# compressor_poc.net
KiCad netlist of a schematic drawn in EAGLE
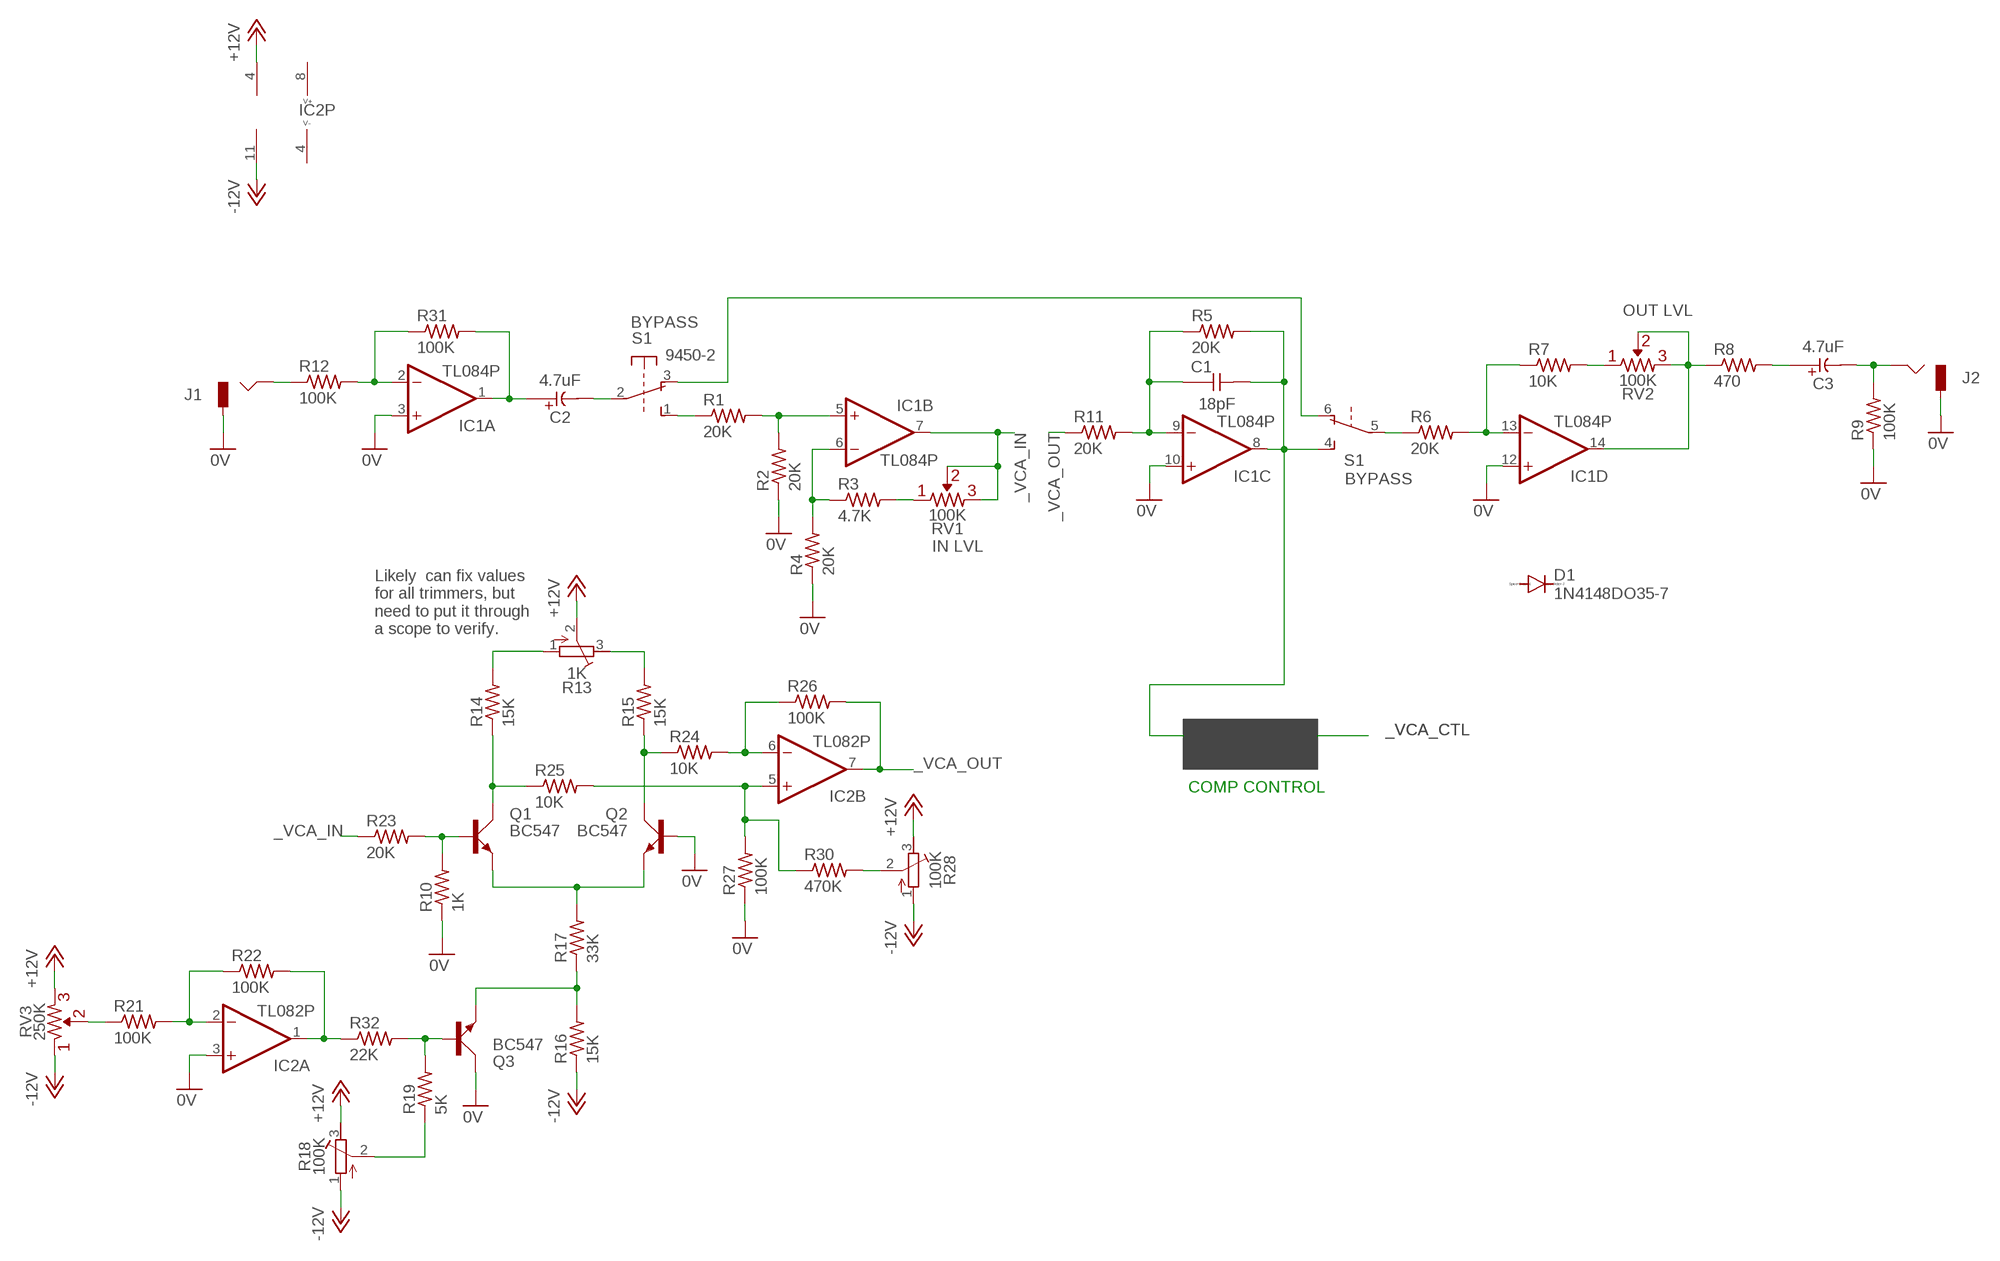
[diagram p0: schematic, sheet 1]

(export (version "E")
  (design (tool "Eeschema 10.0.6"))
  (components
    (comp (ref "C1")
      (value "18pF")
      (footprint "eagle-import:C025-024X044")
      (libsource (lib "eagle-import") (part "CC-US025-024X044"))
    )
    (comp (ref "C2")
      (value "4.7uF")
      (footprint "eagle-import:E2-5")
      (libsource (lib "eagle-import") (part "CE-USE2-5"))
    )
    (comp (ref "C3")
      (value "4.7uF")
      (footprint "eagle-import:E2-5")
      (libsource (lib "eagle-import") (part "CE-USE2-5"))
    )
    (comp (ref "D1")
      (value "1N4148DO35-7")
      (footprint "eagle-import:DO35-7")
      (libsource (lib "eagle-import") (part "1N4148DO35-7"))
    )
    (comp (ref "IC1")
      (value "TL084P")
      (footprint "eagle-import:DIL14")
      (libsource (lib "eagle-import") (part "TL084P"))
    )
    (comp (ref "IC2")
      (value "TL082P")
      (footprint "eagle-import:DIL08")
      (libsource (lib "eagle-import") (part "TL082P"))
    )
    (comp (ref "J1")
      (value "JACK-M")
      (footprint "eagle-import:JACK-M")
      (libsource (lib "eagle-import") (part "JACK-M"))
    )
    (comp (ref "J2")
      (value "JACK-M")
      (footprint "eagle-import:JACK-M")
      (libsource (lib "eagle-import") (part "JACK-M"))
    )
    (comp (ref "Q1")
      (value "BC547")
      (footprint "eagle-import:SOT54A")
      (libsource (lib "eagle-import") (part "BC547"))
    )
    (comp (ref "Q2")
      (value "BC547")
      (footprint "eagle-import:SOT54A")
      (libsource (lib "eagle-import") (part "BC547"))
    )
    (comp (ref "Q3")
      (value "BC547")
      (footprint "eagle-import:SOT54A")
      (libsource (lib "eagle-import") (part "BC547"))
    )
    (comp (ref "R1")
      (value "20K")
      (footprint "eagle-import:0204_7")
      (libsource (lib "eagle-import") (part "R-US_0204/7"))
    )
    (comp (ref "R2")
      (value "20K")
      (footprint "eagle-import:0204_7")
      (libsource (lib "eagle-import") (part "R-US_0204/7"))
    )
    (comp (ref "R3")
      (value "4.7K")
      (footprint "eagle-import:0204_7")
      (libsource (lib "eagle-import") (part "R-US_0204/7"))
    )
    (comp (ref "R4")
      (value "20K")
      (footprint "eagle-import:0204_7")
      (libsource (lib "eagle-import") (part "R-US_0204/7"))
    )
    (comp (ref "R5")
      (value "20K")
      (footprint "eagle-import:0204_7")
      (libsource (lib "eagle-import") (part "R-US_0204/7"))
    )
    (comp (ref "R6")
      (value "20K")
      (footprint "eagle-import:0204_7")
      (libsource (lib "eagle-import") (part "R-US_0204/7"))
    )
    (comp (ref "R7")
      (value "10K")
      (footprint "eagle-import:0204_7")
      (libsource (lib "eagle-import") (part "R-US_0204/7"))
    )
    (comp (ref "R8")
      (value "470")
      (footprint "eagle-import:0204_7")
      (libsource (lib "eagle-import") (part "R-US_0204/7"))
    )
    (comp (ref "R9")
      (value "100K")
      (footprint "eagle-import:0204_7")
      (libsource (lib "eagle-import") (part "R-US_0204/7"))
    )
    (comp (ref "R10")
      (value "1K")
      (footprint "eagle-import:0204_7")
      (libsource (lib "eagle-import") (part "R-US_0204/7"))
    )
    (comp (ref "R11")
      (value "20K")
      (footprint "eagle-import:0204_7")
      (libsource (lib "eagle-import") (part "R-US_0204/7"))
    )
    (comp (ref "R12")
      (value "100K")
      (footprint "eagle-import:0204_7")
      (libsource (lib "eagle-import") (part "R-US_0204/7"))
    )
    (comp (ref "R13")
      (value "1K")
      (footprint "eagle-import:RTRIM3304W")
      (libsource (lib "eagle-import") (part "R-TRIMM3304W"))
    )
    (comp (ref "R14")
      (value "15K")
      (footprint "eagle-import:0204_7")
      (libsource (lib "eagle-import") (part "R-US_0204/7"))
    )
    (comp (ref "R15")
      (value "15K")
      (footprint "eagle-import:0204_7")
      (libsource (lib "eagle-import") (part "R-US_0204/7"))
    )
    (comp (ref "R16")
      (value "15K")
      (footprint "eagle-import:0204_7")
      (libsource (lib "eagle-import") (part "R-US_0204/7"))
    )
    (comp (ref "R17")
      (value "33K")
      (footprint "eagle-import:0204_7")
      (libsource (lib "eagle-import") (part "R-US_0204/7"))
    )
    (comp (ref "R18")
      (value "100K")
      (footprint "eagle-import:RTRIM3304W")
      (libsource (lib "eagle-import") (part "R-TRIMM3304W"))
    )
    (comp (ref "R19")
      (value "5K")
      (footprint "eagle-import:0204_7")
      (libsource (lib "eagle-import") (part "R-US_0204/7"))
    )
    (comp (ref "R21")
      (value "100K")
      (footprint "eagle-import:0204_7")
      (libsource (lib "eagle-import") (part "R-US_0204/7"))
    )
    (comp (ref "R22")
      (value "100K")
      (footprint "eagle-import:0204_7")
      (libsource (lib "eagle-import") (part "R-US_0204/7"))
    )
    (comp (ref "R23")
      (value "20K")
      (footprint "eagle-import:0204_7")
      (libsource (lib "eagle-import") (part "R-US_0204/7"))
    )
    (comp (ref "R24")
      (value "10K")
      (footprint "eagle-import:0204_7")
      (libsource (lib "eagle-import") (part "R-US_0204/7"))
    )
    (comp (ref "R25")
      (value "10K")
      (footprint "eagle-import:0204_7")
      (libsource (lib "eagle-import") (part "R-US_0204/7"))
    )
    (comp (ref "R26")
      (value "100K")
      (footprint "eagle-import:0204_7")
      (libsource (lib "eagle-import") (part "R-US_0204/7"))
    )
    (comp (ref "R27")
      (value "100K")
      (footprint "eagle-import:0204_7")
      (libsource (lib "eagle-import") (part "R-US_0204/7"))
    )
    (comp (ref "R28")
      (value "100K")
      (footprint "eagle-import:RTRIM3304W")
      (libsource (lib "eagle-import") (part "R-TRIMM3304W"))
    )
    (comp (ref "R30")
      (value "470K")
      (footprint "eagle-import:0204_7")
      (libsource (lib "eagle-import") (part "R-US_0204/7"))
    )
    (comp (ref "R31")
      (value "100K")
      (footprint "eagle-import:0204_7")
      (libsource (lib "eagle-import") (part "R-US_0204/7"))
    )
    (comp (ref "R32")
      (value "22K")
      (footprint "eagle-import:0204_7")
      (libsource (lib "eagle-import") (part "R-US_0204/7"))
    )
    (comp (ref "RV1")
      (value "100K")
      (footprint "eagle-import:R-VAR")
      (libsource (lib "eagle-import") (part "R-VAR"))
    )
    (comp (ref "RV2")
      (value "100K")
      (footprint "eagle-import:R-VAR")
      (libsource (lib "eagle-import") (part "R-VAR"))
    )
    (comp (ref "RV3")
      (value "250K")
      (footprint "eagle-import:R-VAR")
      (libsource (lib "eagle-import") (part "R-VAR"))
    )
    (comp (ref "S1")
      (value "9450-2")
      (footprint "eagle-import:9450-2")
      (libsource (lib "eagle-import") (part "9450-2"))
    )
  )
  (nets
    (net (code "1") (name "+12V") (class "Default")
      (node (ref "IC1") (pin "4") (pinfunction "V+_4") (pintype "power_in"))
      (node (ref "R13") (pin "2") (pinfunction "S_2") (pintype "passive"))
      (node (ref "R18") (pin "3") (pinfunction "A_3") (pintype "passive"))
      (node (ref "R28") (pin "3") (pinfunction "A_3") (pintype "passive"))
      (node (ref "RV3") (pin "R2") (pinfunction "2_R2") (pintype "passive"))
    )
    (net (code "2") (name "-12V") (class "Default")
      (node (ref "IC1") (pin "11") (pinfunction "V-_11") (pintype "power_in"))
      (node (ref "R16") (pin "1") (pinfunction "1_1") (pintype "passive"))
      (node (ref "R18") (pin "1") (pinfunction "E_1") (pintype "passive"))
      (node (ref "R28") (pin "1") (pinfunction "E_1") (pintype "passive"))
      (node (ref "RV3") (pin "R1") (pinfunction "1_R1") (pintype "passive"))
    )
    (net (code "3") (name "/V+") (class "Default")
      (node (ref "IC2") (pin "8") (pinfunction "V+_8") (pintype "power_in"))
    )
    (net (code "4") (name "/V-") (class "Default")
      (node (ref "IC2") (pin "4") (pinfunction "V-_4") (pintype "power_in"))
    )
    (net (code "6") (name "/_VCA_IN") (class "Default")
      (node (ref "IC1") (pin "7") (pinfunction "OUT_7") (pintype "output"))
      (node (ref "R23") (pin "1") (pinfunction "1_1") (pintype "passive"))
      (node (ref "RV1") (pin "R2") (pinfunction "2_R2") (pintype "passive"))
      (node (ref "RV1") (pin "VAR") (pinfunction "P$1_VAR") (pintype "passive"))
    )
    (net (code "7") (name "/_VCA_OUT") (class "Default")
      (node (ref "IC2") (pin "7") (pinfunction "OUT_7") (pintype "output"))
      (node (ref "R11") (pin "1") (pinfunction "1_1") (pintype "passive"))
      (node (ref "R26") (pin "2") (pinfunction "2_2") (pintype "passive"))
    )
    (net (code "8") (name "0V") (class "Default")
      (node (ref "IC1") (pin "10") (pinfunction "+IN_10") (pintype "input"))
      (node (ref "IC1") (pin "12") (pinfunction "+IN_12") (pintype "input"))
      (node (ref "IC1") (pin "3") (pinfunction "+IN_3") (pintype "input"))
      (node (ref "IC2") (pin "3") (pinfunction "+IN_3") (pintype "input"))
      (node (ref "J1") (pin "GND") (pinfunction "GND_GND") (pintype "bidirectional"))
      (node (ref "J2") (pin "GND") (pinfunction "GND_GND") (pintype "bidirectional"))
      (node (ref "Q2") (pin "B") (pinfunction "B_B") (pintype "passive"))
      (node (ref "Q3") (pin "C") (pinfunction "C_C") (pintype "passive"))
      (node (ref "R10") (pin "1") (pinfunction "1_1") (pintype "passive"))
      (node (ref "R2") (pin "1") (pinfunction "1_1") (pintype "passive"))
      (node (ref "R27") (pin "1") (pinfunction "1_1") (pintype "passive"))
      (node (ref "R4") (pin "1") (pinfunction "1_1") (pintype "passive"))
      (node (ref "R9") (pin "1") (pinfunction "1_1") (pintype "passive"))
    )
    (net (code "9") (name "Net-(C3-Pad+)") (class "Default")
      (node (ref "C3") (pin "+") (pinfunction "+_+") (pintype "passive"))
      (node (ref "R8") (pin "2") (pinfunction "2_2") (pintype "passive"))
    )
    (net (code "10") (name "Net-(C3-Pad-)") (class "Default")
      (node (ref "C3") (pin "-") (pinfunction "-_-") (pintype "passive"))
      (node (ref "J2") (pin "HOT") (pinfunction "HOT_HOT") (pintype "bidirectional"))
      (node (ref "R9") (pin "2") (pinfunction "2_2") (pintype "passive"))
    )
    (net (code "11") (name "Net-(IC1A--IN)") (class "Default")
      (node (ref "IC1") (pin "2") (pinfunction "-IN_2") (pintype "input"))
      (node (ref "R12") (pin "2") (pinfunction "2_2") (pintype "passive"))
      (node (ref "R31") (pin "1") (pinfunction "1_1") (pintype "passive"))
    )
    (net (code "12") (name "Net-(IC1A-OUT)") (class "Default")
      (node (ref "C2") (pin "+") (pinfunction "+_+") (pintype "passive"))
      (node (ref "IC1") (pin "1") (pinfunction "OUT_1") (pintype "output"))
      (node (ref "R31") (pin "2") (pinfunction "2_2") (pintype "passive"))
    )
    (net (code "13") (name "Net-(IC1B-+IN)") (class "Default")
      (node (ref "IC1") (pin "5") (pinfunction "+IN_5") (pintype "input"))
      (node (ref "R1") (pin "2") (pinfunction "2_2") (pintype "passive"))
      (node (ref "R2") (pin "2") (pinfunction "2_2") (pintype "passive"))
    )
    (net (code "14") (name "Net-(IC1B--IN)") (class "Default")
      (node (ref "IC1") (pin "6") (pinfunction "-IN_6") (pintype "input"))
      (node (ref "R3") (pin "1") (pinfunction "1_1") (pintype "passive"))
      (node (ref "R4") (pin "2") (pinfunction "2_2") (pintype "passive"))
    )
    (net (code "15") (name "Net-(IC1C--IN)") (class "Default")
      (node (ref "C1") (pin "1") (pinfunction "1_1") (pintype "passive"))
      (node (ref "IC1") (pin "9") (pinfunction "-IN_9") (pintype "input"))
      (node (ref "R11") (pin "2") (pinfunction "2_2") (pintype "passive"))
      (node (ref "R5") (pin "1") (pinfunction "1_1") (pintype "passive"))
    )
    (net (code "16") (name "Net-(IC1C-OUT)") (class "Default")
      (node (ref "C1") (pin "2") (pinfunction "2_2") (pintype "passive"))
      (node (ref "IC1") (pin "8") (pinfunction "OUT_8") (pintype "output"))
      (node (ref "R5") (pin "2") (pinfunction "2_2") (pintype "passive"))
      (node (ref "S1") (pin "4") (pinfunction "S_4") (pintype "passive"))
    )
    (net (code "17") (name "Net-(IC1D--IN)") (class "Default")
      (node (ref "IC1") (pin "13") (pinfunction "-IN_13") (pintype "input"))
      (node (ref "R6") (pin "2") (pinfunction "2_2") (pintype "passive"))
      (node (ref "R7") (pin "1") (pinfunction "1_1") (pintype "passive"))
    )
    (net (code "18") (name "Net-(IC1D-OUT)") (class "Default")
      (node (ref "IC1") (pin "14") (pinfunction "OUT_14") (pintype "output"))
      (node (ref "R8") (pin "1") (pinfunction "1_1") (pintype "passive"))
      (node (ref "RV2") (pin "R2") (pinfunction "2_R2") (pintype "passive"))
      (node (ref "RV2") (pin "VAR") (pinfunction "P$1_VAR") (pintype "passive"))
    )
    (net (code "19") (name "Net-(IC2A--IN)") (class "Default")
      (node (ref "IC2") (pin "2") (pinfunction "-IN_2") (pintype "input"))
      (node (ref "R21") (pin "2") (pinfunction "2_2") (pintype "passive"))
      (node (ref "R22") (pin "1") (pinfunction "1_1") (pintype "passive"))
    )
    (net (code "20") (name "Net-(IC2A-OUT)") (class "Default")
      (node (ref "IC2") (pin "1") (pinfunction "OUT_1") (pintype "output"))
      (node (ref "R22") (pin "2") (pinfunction "2_2") (pintype "passive"))
      (node (ref "R32") (pin "1") (pinfunction "1_1") (pintype "passive"))
    )
    (net (code "21") (name "Net-(IC2B-+IN)") (class "Default")
      (node (ref "IC2") (pin "5") (pinfunction "+IN_5") (pintype "input"))
      (node (ref "R25") (pin "2") (pinfunction "2_2") (pintype "passive"))
      (node (ref "R27") (pin "2") (pinfunction "2_2") (pintype "passive"))
      (node (ref "R30") (pin "1") (pinfunction "1_1") (pintype "passive"))
    )
    (net (code "22") (name "Net-(IC2B--IN)") (class "Default")
      (node (ref "IC2") (pin "6") (pinfunction "-IN_6") (pintype "input"))
      (node (ref "R24") (pin "2") (pinfunction "2_2") (pintype "passive"))
      (node (ref "R26") (pin "1") (pinfunction "1_1") (pintype "passive"))
    )
    (net (code "23") (name "Net-(J1-PadHOT)") (class "Default")
      (node (ref "J1") (pin "HOT") (pinfunction "HOT_HOT") (pintype "bidirectional"))
      (node (ref "R12") (pin "1") (pinfunction "1_1") (pintype "passive"))
    )
    (net (code "24") (name "Net-(Q1-PadB)") (class "Default")
      (node (ref "Q1") (pin "B") (pinfunction "B_B") (pintype "passive"))
      (node (ref "R10") (pin "2") (pinfunction "2_2") (pintype "passive"))
      (node (ref "R23") (pin "2") (pinfunction "2_2") (pintype "passive"))
    )
    (net (code "25") (name "Net-(Q1-PadC)") (class "Default")
      (node (ref "Q1") (pin "C") (pinfunction "C_C") (pintype "passive"))
      (node (ref "R14") (pin "1") (pinfunction "1_1") (pintype "passive"))
      (node (ref "R25") (pin "1") (pinfunction "1_1") (pintype "passive"))
    )
    (net (code "26") (name "Net-(Q1-PadE)") (class "Default")
      (node (ref "Q1") (pin "E") (pinfunction "E_E") (pintype "passive"))
      (node (ref "Q2") (pin "E") (pinfunction "E_E") (pintype "passive"))
      (node (ref "R17") (pin "2") (pinfunction "2_2") (pintype "passive"))
    )
    (net (code "27") (name "Net-(Q2-PadC)") (class "Default")
      (node (ref "Q2") (pin "C") (pinfunction "C_C") (pintype "passive"))
      (node (ref "R15") (pin "1") (pinfunction "1_1") (pintype "passive"))
      (node (ref "R24") (pin "1") (pinfunction "1_1") (pintype "passive"))
    )
    (net (code "28") (name "Net-(Q3-PadB)") (class "Default")
      (node (ref "Q3") (pin "B") (pinfunction "B_B") (pintype "passive"))
      (node (ref "R19") (pin "2") (pinfunction "2_2") (pintype "passive"))
      (node (ref "R32") (pin "2") (pinfunction "2_2") (pintype "passive"))
    )
    (net (code "29") (name "Net-(Q3-PadE)") (class "Default")
      (node (ref "Q3") (pin "E") (pinfunction "E_E") (pintype "passive"))
      (node (ref "R16") (pin "2") (pinfunction "2_2") (pintype "passive"))
      (node (ref "R17") (pin "1") (pinfunction "1_1") (pintype "passive"))
    )
    (net (code "30") (name "Net-(R13-A)") (class "Default")
      (node (ref "R13") (pin "3") (pinfunction "A_3") (pintype "passive"))
      (node (ref "R15") (pin "2") (pinfunction "2_2") (pintype "passive"))
    )
    (net (code "31") (name "Net-(R13-E)") (class "Default")
      (node (ref "R13") (pin "1") (pinfunction "E_1") (pintype "passive"))
      (node (ref "R14") (pin "2") (pinfunction "2_2") (pintype "passive"))
    )
    (net (code "32") (name "Net-(R18-S)") (class "Default")
      (node (ref "R18") (pin "2") (pinfunction "S_2") (pintype "passive"))
      (node (ref "R19") (pin "1") (pinfunction "1_1") (pintype "passive"))
    )
    (net (code "33") (name "Net-(R28-S)") (class "Default")
      (node (ref "R28") (pin "2") (pinfunction "S_2") (pintype "passive"))
      (node (ref "R30") (pin "2") (pinfunction "2_2") (pintype "passive"))
    )
    (net (code "34") (name "Net-(RV1-1)") (class "Default")
      (node (ref "R3") (pin "2") (pinfunction "2_2") (pintype "passive"))
      (node (ref "RV1") (pin "R1") (pinfunction "1_R1") (pintype "passive"))
    )
    (net (code "35") (name "Net-(RV2-1)") (class "Default")
      (node (ref "R7") (pin "2") (pinfunction "2_2") (pintype "passive"))
      (node (ref "RV2") (pin "R1") (pinfunction "1_R1") (pintype "passive"))
    )
    (net (code "36") (name "Net-(RV3-P$1)") (class "Default")
      (node (ref "R21") (pin "1") (pinfunction "1_1") (pintype "passive"))
      (node (ref "RV3") (pin "VAR") (pinfunction "P$1_VAR") (pintype "passive"))
    )
    (net (code "37") (name "Net-(S1A-O)") (class "Default")
      (node (ref "S1") (pin "3") (pinfunction "O_3") (pintype "passive"))
      (node (ref "S1") (pin "6") (pinfunction "O_6") (pintype "passive"))
    )
    (net (code "38") (name "Net-(S1A-P)") (class "Default")
      (node (ref "C2") (pin "-") (pinfunction "-_-") (pintype "passive"))
      (node (ref "S1") (pin "2") (pinfunction "P_2") (pintype "passive"))
    )
    (net (code "39") (name "Net-(S1A-S)") (class "Default")
      (node (ref "R1") (pin "1") (pinfunction "1_1") (pintype "passive"))
      (node (ref "S1") (pin "1") (pinfunction "S_1") (pintype "passive"))
    )
    (net (code "40") (name "Net-(S1B-P)") (class "Default")
      (node (ref "R6") (pin "1") (pinfunction "1_1") (pintype "passive"))
      (node (ref "S1") (pin "5") (pinfunction "P_5") (pintype "passive"))
    )
    (net (code "41") (name "unconnected-(D1-PadA)") (class "Default")
      (node (ref "D1") (pin "A") (pinfunction "A_A") (pintype "passive"))
    )
    (net (code "42") (name "unconnected-(D1-PadC)") (class "Default")
      (node (ref "D1") (pin "C") (pinfunction "C_C") (pintype "passive"))
    )
  )
)
